# 15_PowerSupply.net
KiCad netlist of a schematic drawn in Altium Designer
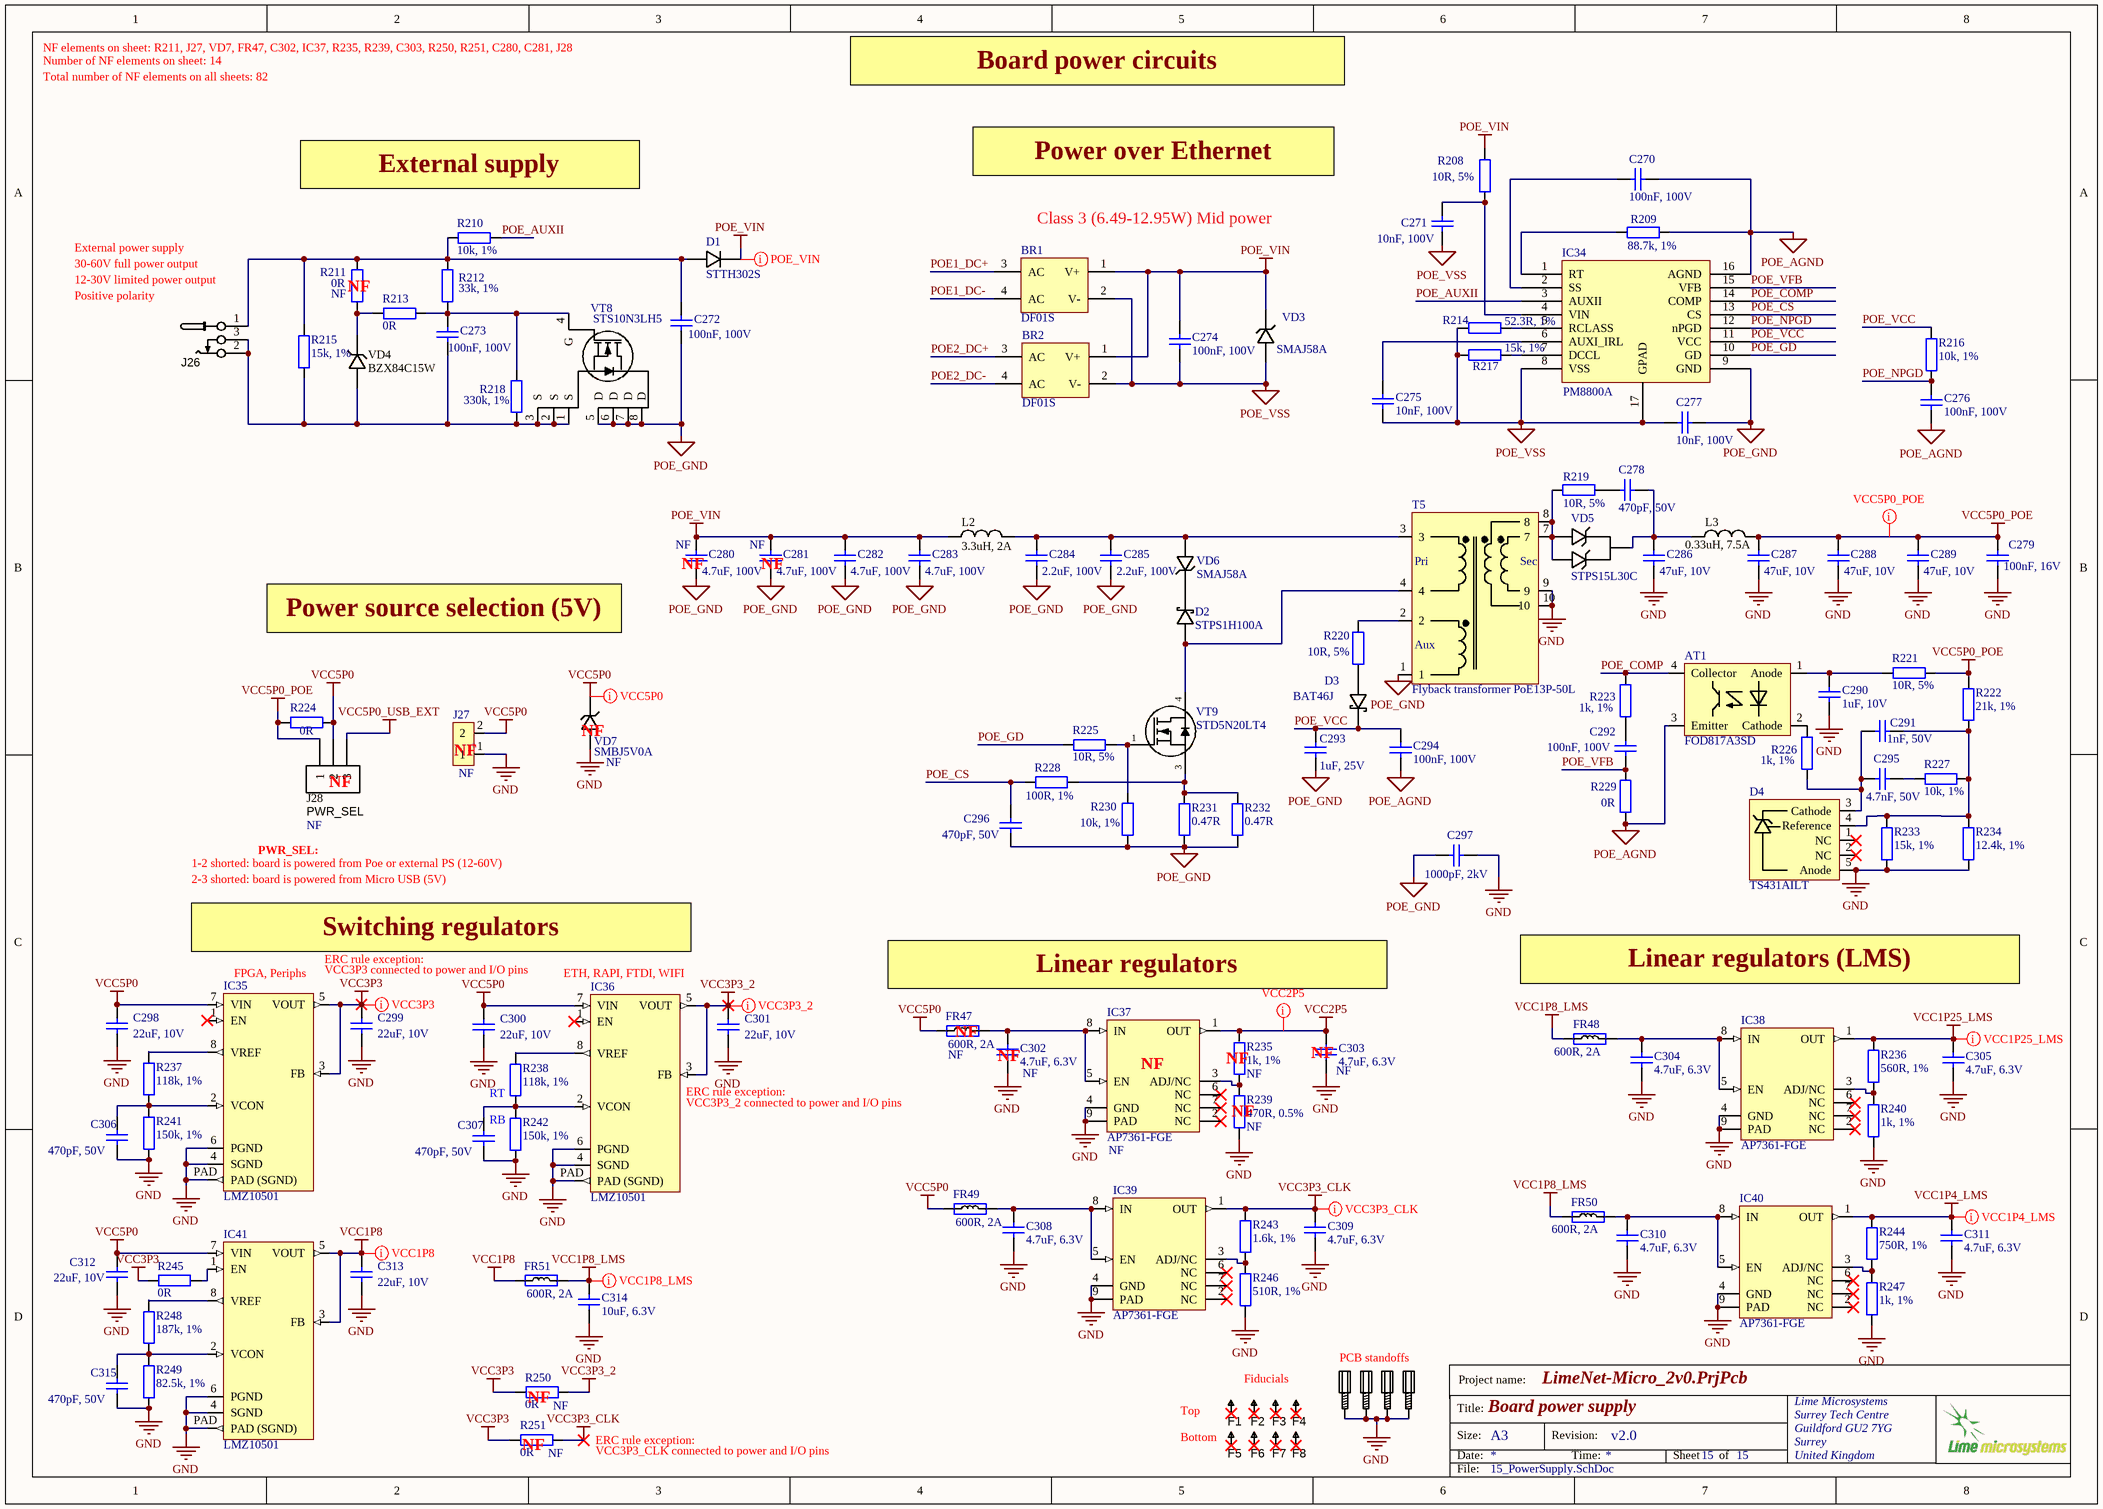
[diagram p0: 15_PowerSupply.SchDoc]

(export (version "E")
  (design (tool "Eeschema 10.0.6"))
  (components
    (comp (ref "AT1")
      (value "FOD817A3SD")
      (footprint "FOD817A3SD_optoisolator_FOD817")
      (fields (field (name "MANUFACTURER") "ON Semiconductor / Fairchild"))
      (libsource (lib "LimeMicroAltiumLib_schLib_r01") (part "FOD817A3SD_optoisolator"))
    )
    (comp (ref "BR1")
      (value "DF01S")
      (footprint "DF01S-T_RECTIFIER_BRIDGE_v1")
      (description "Diode Bridge")
      (fields (field (name "MANUFACTURER") "Diodes Incorporated"))
      (libsource (lib "Biblioteka_Ethernet") (part "Bridge2"))
    )
    (comp (ref "BR2")
      (value "DF01S")
      (footprint "DF01S-T_RECTIFIER_BRIDGE_v1")
      (description "Diode Bridge")
      (fields (field (name "MANUFACTURER") "Diodes Incorporated"))
      (libsource (lib "Biblioteka_Ethernet") (part "Bridge2"))
    )
    (comp (ref "C270")
      (value "100nF, 100V")
      (footprint "CAP0805")
      (fields
        (field (name "MANUFACTURER") "Murata Electronics North America")
        (field (name "TOLERANCE") "±10%")
      )
      (libsource (lib "LimeMicroAltium") (part "Cap_0805"))
    )
    (comp (ref "C271")
      (value "10nF, 100V")
      (footprint "CAP0603")
      (fields
        (field (name "TOLERANCE") "±10%")
        (field (name "MANUFACTURER") "Murata Electronics North America")
      )
      (libsource (lib "LimeFPGAboard_schLib") (part "Cap_0603"))
    )
    (comp (ref "C272")
      (value "100nF, 100V")
      (footprint "CAP0805")
      (fields
        (field (name "MANUFACTURER") "Murata Electronics North America")
        (field (name "TOLERANCE") "±10%")
      )
      (libsource (lib "LimeMicroAltium") (part "Cap_0805"))
    )
    (comp (ref "C273")
      (value "100nF, 100V")
      (footprint "CAP0805")
      (fields
        (field (name "MANUFACTURER") "Murata Electronics North America")
        (field (name "TOLERANCE") "±10%")
      )
      (libsource (lib "LimeMicroAltium") (part "Cap_0805"))
    )
    (comp (ref "C274")
      (value "100nF, 100V")
      (footprint "CAP0805")
      (fields
        (field (name "MANUFACTURER") "Murata Electronics North America")
        (field (name "TOLERANCE") "±10%")
      )
      (libsource (lib "LimeMicroAltium") (part "Cap_0805"))
    )
    (comp (ref "C275")
      (value "10nF, 100V")
      (footprint "CAP0603")
      (fields
        (field (name "TOLERANCE") "±10%")
        (field (name "MANUFACTURER") "Murata Electronics North America")
      )
      (libsource (lib "LimeFPGAboard_schLib") (part "Cap_0603"))
    )
    (comp (ref "C276")
      (value "100nF, 100V")
      (footprint "CAP0805")
      (fields
        (field (name "MANUFACTURER") "Murata Electronics North America")
        (field (name "TOLERANCE") "±10%")
      )
      (libsource (lib "LimeMicroAltium") (part "Cap_0805"))
    )
    (comp (ref "C277")
      (value "10nF, 100V")
      (footprint "CAP0603")
      (fields
        (field (name "TOLERANCE") "±10%")
        (field (name "MANUFACTURER") "Murata Electronics North America")
      )
      (libsource (lib "LimeFPGAboard_schLib") (part "Cap_0603"))
    )
    (comp (ref "C278")
      (value "470pF, 50V")
      (footprint "CAP0402")
      (fields
        (field (name "MANUFACTURER PART NUMBER") "C1005C0G1H471J050BA")
        (field (name "TOLERANCE") "±5%")
        (field (name "MANUFACTURER") "TDK Corporation")
      )
      (libsource (lib "LimeMicroAltiumLib_schLib") (part "Cap_0402"))
    )
    (comp (ref "C279")
      (value "100nF, 16V")
      (footprint "CAP0402")
      (fields
        (field (name "MANUFACTURER") "Murata Electronics")
        (field (name "TOLERANCE") "10 %")
        (field (name "MANUFACTURER PART NUMBER") "GRM155R71C104KA88D")
      )
      (libsource (lib "LimeMicroAltiumLib_schLib") (part "Cap_0402"))
    )
    (comp (ref "C280")
      (value "4.7uF, 100V")
      (footprint "CAP1210")
      (fields
        (field (name "ASSEMBLY INFO") "NF")
        (field (name "MANUFACTURER") "TDK Corporation")
        (field (name "TOLERANCE") "±20%")
      )
      (libsource (lib "LimeFPGAboard_schLib") (part "Cap_1206"))
    )
    (comp (ref "C281")
      (value "4.7uF, 100V")
      (footprint "CAP1210")
      (fields
        (field (name "ASSEMBLY INFO") "NF")
        (field (name "MANUFACTURER") "TDK Corporation")
        (field (name "TOLERANCE") "±20%")
      )
      (libsource (lib "LimeFPGAboard_schLib") (part "Cap_1206"))
    )
    (comp (ref "C282")
      (value "4.7uF, 100V")
      (footprint "CAP1210")
      (fields (field (name "MANUFACTURER") "TDK Corporation") (field (name "TOLERANCE") "±20%"))
      (libsource (lib "LimeFPGAboard_schLib") (part "Cap_1206"))
    )
    (comp (ref "C283")
      (value "4.7uF, 100V")
      (footprint "CAP1210")
      (fields (field (name "MANUFACTURER") "TDK Corporation") (field (name "TOLERANCE") "±20%"))
      (libsource (lib "LimeFPGAboard_schLib") (part "Cap_1206"))
    )
    (comp (ref "C284")
      (value "2.2uF, 100V")
      (footprint "CAP1206")
      (fields (field (name "MANUFACTURER") "TDK Corporation") (field (name "TOLERANCE") "±10%"))
      (libsource (lib "LimeFPGAboard_schLib") (part "Cap_1206"))
    )
    (comp (ref "C285")
      (value "2.2uF, 100V")
      (footprint "CAP1206")
      (fields (field (name "MANUFACTURER") "TDK Corporation") (field (name "TOLERANCE") "±10%"))
      (libsource (lib "LimeFPGAboard_schLib") (part "Cap_1206"))
    )
    (comp (ref "C286")
      (value "47uF, 10V")
      (footprint "CAP1206")
      (fields (field (name "TOLERANCE") "±20%") (field (name "MANUFACTURER") "TDK Corporation"))
      (libsource (lib "LimeFPGAboard_schLib") (part "Cap_1206"))
    )
    (comp (ref "C287")
      (value "47uF, 10V")
      (footprint "CAP1206")
      (fields (field (name "TOLERANCE") "±20%") (field (name "MANUFACTURER") "TDK Corporation"))
      (libsource (lib "LimeFPGAboard_schLib") (part "Cap_1206"))
    )
    (comp (ref "C288")
      (value "47uF, 10V")
      (footprint "CAP1206")
      (fields (field (name "TOLERANCE") "±20%") (field (name "MANUFACTURER") "TDK Corporation"))
      (libsource (lib "LimeFPGAboard_schLib") (part "Cap_1206"))
    )
    (comp (ref "C289")
      (value "47uF, 10V")
      (footprint "CAP1206")
      (fields (field (name "TOLERANCE") "±20%") (field (name "MANUFACTURER") "TDK Corporation"))
      (libsource (lib "LimeFPGAboard_schLib") (part "Cap_1206"))
    )
    (comp (ref "C290")
      (value "1uF, 10V")
      (footprint "CAP0402")
      (description "CAP CER 1UF 10V X5R 0402")
      (fields
        (field (name "MANUFACTURER") "Yageo")
        (field (name "MANUFACTURER PART NUMBER") "CC0402MRX5R6BB105")
      )
      (libsource (lib "LimeMicroAltiumLib_schLib") (part "Cap_0402"))
    )
    (comp (ref "C291")
      (value "1nF, 50V")
      (footprint "CAP0402")
      (fields
        (field (name "TOLERANCE") "±10%")
        (field (name "MANUFACTURER") "Murata Electronics North America")
      )
      (libsource (lib "LimeMicroAltiumLib_schLib") (part "Cap_0402"))
    )
    (comp (ref "C292")
      (value "100nF, 100V")
      (footprint "CAP0805")
      (fields
        (field (name "MANUFACTURER") "Murata Electronics North America")
        (field (name "TOLERANCE") "±10%")
      )
      (libsource (lib "LimeMicroAltium") (part "Cap_0805"))
    )
    (comp (ref "C293")
      (value "1uF, 25V")
      (footprint "CAP0603")
      (fields (field (name "MANUFACTURER") "Samsung Electro-Mechanics") (field (name "TOLERANCE") "±10%"))
      (libsource (lib "LimeMicroAltiumLib_schLib") (part "Cap_0603"))
    )
    (comp (ref "C294")
      (value "100nF, 100V")
      (footprint "CAP0805")
      (fields
        (field (name "MANUFACTURER") "Murata Electronics North America")
        (field (name "TOLERANCE") "±10%")
      )
      (libsource (lib "LimeMicroAltium") (part "Cap_0805"))
    )
    (comp (ref "C295")
      (value "4.7nF, 50V")
      (footprint "CAP0402")
      (fields
        (field (name "TOLERANCE") "±10%")
        (field (name "MANUFACTURER") "Murata Electronics North America")
      )
      (libsource (lib "LimeMicroAltiumLib_schLib") (part "Cap_0402"))
    )
    (comp (ref "C296")
      (value "470pF, 50V")
      (footprint "CAP0402")
      (fields
        (field (name "MANUFACTURER PART NUMBER") "C1005C0G1H471J050BA")
        (field (name "TOLERANCE") "±5%")
        (field (name "MANUFACTURER") "TDK Corporation")
      )
      (libsource (lib "LimeMicroAltiumLib_schLib") (part "Cap_0402"))
    )
    (comp (ref "C297")
      (value "1000pF, 2kV")
      (footprint "CAP1812")
      (fields (field (name "MANUFACTURER") "KEMET") (field (name "TOLERANCE") "±10%"))
      (libsource (lib "LimeFPGAboard_schLib") (part "Cap_1206"))
    )
    (comp (ref "C298")
      (value "22uF, 10V")
      (footprint "CAP0603")
      (fields (field (name "TOLERANCE") "20 %") (field (name "MANUFACTURER") "TDK Corporation"))
      (libsource (lib "LimeFPGAboard_schLib") (part "Cap_0603"))
    )
    (comp (ref "C299")
      (value "22uF, 10V")
      (footprint "CAP0603")
      (fields (field (name "TOLERANCE") "20 %") (field (name "MANUFACTURER") "TDK Corporation"))
      (libsource (lib "LimeFPGAboard_schLib") (part "Cap_0603"))
    )
    (comp (ref "C300")
      (value "22uF, 10V")
      (footprint "CAP0603")
      (fields (field (name "TOLERANCE") "20 %") (field (name "MANUFACTURER") "TDK Corporation"))
      (libsource (lib "LimeFPGAboard_schLib") (part "Cap_0603"))
    )
    (comp (ref "C301")
      (value "22uF, 10V")
      (footprint "CAP0603")
      (fields (field (name "TOLERANCE") "20 %") (field (name "MANUFACTURER") "TDK Corporation"))
      (libsource (lib "LimeFPGAboard_schLib") (part "Cap_0603"))
    )
    (comp (ref "C302")
      (value "4.7uF, 6.3V")
      (footprint "CAP0402")
      (fields
        (field (name "ASSEMBLY INFO") "NF")
        (field (name "MANUFACTURER") "Murata Electronics North America")
        (field (name "TOLERANCE") "±20%")
        (field (name "MANUFACTURER PART NUMBER") "GRM155R60J475ME87D")
      )
      (libsource (lib "LimeMicroAltiumLib_schLib") (part "Cap_0402"))
    )
    (comp (ref "C303")
      (value "4.7uF, 6.3V")
      (footprint "CAP0402")
      (fields
        (field (name "ASSEMBLY INFO") "NF")
        (field (name "MANUFACTURER") "Murata Electronics North America")
        (field (name "TOLERANCE") "±20%")
        (field (name "MANUFACTURER PART NUMBER") "GRM155R60J475ME87D")
      )
      (libsource (lib "LimeMicroAltiumLib_schLib") (part "Cap_0402"))
    )
    (comp (ref "C304")
      (value "4.7uF, 6.3V")
      (footprint "CAP0402")
      (fields
        (field (name "MANUFACTURER") "Murata Electronics North America")
        (field (name "TOLERANCE") "±20%")
        (field (name "MANUFACTURER PART NUMBER") "GRM155R60J475ME87D")
      )
      (libsource (lib "LimeMicroAltiumLib_schLib") (part "Cap_0402"))
    )
    (comp (ref "C305")
      (value "4.7uF, 6.3V")
      (footprint "CAP0402")
      (fields
        (field (name "MANUFACTURER") "Murata Electronics North America")
        (field (name "TOLERANCE") "±20%")
        (field (name "MANUFACTURER PART NUMBER") "GRM155R60J475ME87D")
      )
      (libsource (lib "LimeMicroAltiumLib_schLib") (part "Cap_0402"))
    )
    (comp (ref "C306")
      (value "470pF, 50V")
      (footprint "CAP0402")
      (fields
        (field (name "MANUFACTURER PART NUMBER") "C1005C0G1H471J050BA")
        (field (name "TOLERANCE") "±5%")
        (field (name "MANUFACTURER") "TDK Corporation")
      )
      (libsource (lib "LimeMicroAltiumLib_schLib") (part "Cap_0402"))
    )
    (comp (ref "C307")
      (value "470pF, 50V")
      (footprint "CAP0402")
      (fields
        (field (name "MANUFACTURER PART NUMBER") "C1005C0G1H471J050BA")
        (field (name "TOLERANCE") "±5%")
        (field (name "MANUFACTURER") "TDK Corporation")
      )
      (libsource (lib "LimeMicroAltiumLib_schLib") (part "Cap_0402"))
    )
    (comp (ref "C308")
      (value "4.7uF, 6.3V")
      (footprint "CAP0402")
      (fields
        (field (name "MANUFACTURER") "Murata Electronics North America")
        (field (name "TOLERANCE") "±20%")
        (field (name "MANUFACTURER PART NUMBER") "GRM155R60J475ME87D")
      )
      (libsource (lib "LimeMicroAltiumLib_schLib") (part "Cap_0402"))
    )
    (comp (ref "C309")
      (value "4.7uF, 6.3V")
      (footprint "CAP0402")
      (fields
        (field (name "MANUFACTURER") "Murata Electronics North America")
        (field (name "TOLERANCE") "±20%")
        (field (name "MANUFACTURER PART NUMBER") "GRM155R60J475ME87D")
      )
      (libsource (lib "LimeMicroAltiumLib_schLib") (part "Cap_0402"))
    )
    (comp (ref "C310")
      (value "4.7uF, 6.3V")
      (footprint "CAP0402")
      (fields
        (field (name "MANUFACTURER") "Murata Electronics North America")
        (field (name "TOLERANCE") "±20%")
        (field (name "MANUFACTURER PART NUMBER") "GRM155R60J475ME87D")
      )
      (libsource (lib "LimeMicroAltiumLib_schLib") (part "Cap_0402"))
    )
    (comp (ref "C311")
      (value "4.7uF, 6.3V")
      (footprint "CAP0402")
      (fields
        (field (name "MANUFACTURER") "Murata Electronics North America")
        (field (name "TOLERANCE") "±20%")
        (field (name "MANUFACTURER PART NUMBER") "GRM155R60J475ME87D")
      )
      (libsource (lib "LimeMicroAltiumLib_schLib") (part "Cap_0402"))
    )
    (comp (ref "C312")
      (value "22uF, 10V")
      (footprint "CAP0603")
      (fields (field (name "TOLERANCE") "20 %") (field (name "MANUFACTURER") "TDK Corporation"))
      (libsource (lib "LimeFPGAboard_schLib") (part "Cap_0603"))
    )
    (comp (ref "C313")
      (value "22uF, 10V")
      (footprint "CAP0603")
      (fields (field (name "TOLERANCE") "20 %") (field (name "MANUFACTURER") "TDK Corporation"))
      (libsource (lib "LimeFPGAboard_schLib") (part "Cap_0603"))
    )
    (comp (ref "C314")
      (value "10uF, 6.3V")
      (footprint "CAP0603")
      (fields (field (name "TOLERANCE") "±20%") (field (name "MANUFACTURER") "Yageo"))
      (libsource (lib "LimeFPGAboard_schLib") (part "Cap_0603"))
    )
    (comp (ref "C315")
      (value "470pF, 50V")
      (footprint "CAP0402")
      (fields
        (field (name "MANUFACTURER PART NUMBER") "C1005C0G1H471J050BA")
        (field (name "TOLERANCE") "±5%")
        (field (name "MANUFACTURER") "TDK Corporation")
      )
      (libsource (lib "LimeMicroAltiumLib_schLib") (part "Cap_0402"))
    )
    (comp (ref "D1")
      (value "STTH302S")
      (footprint "STTH302S_diode")
      (fields (field (name "MANUFACTURER") "STMicroelectronics"))
      (libsource (lib "LimeMicroAltiumLib_schLib_r01") (part "STTH302S_diode"))
    )
    (comp (ref "D2")
      (value "STPS1H100A")
      (footprint "STPS1H100A_shottky_diode")
      (fields (field (name "MANUFACTURER") "STMicroelectronics"))
      (libsource (lib "LimeMicroAltiumLib_schLib_r01") (part "STPS1H100A_shottky_diode"))
    )
    (comp (ref "D3")
      (value "BAT46J")
      (footprint "BAT46JFILM_shottky_diode_SOD323")
      (fields (field (name "MANUFACTURER") "STMicroelectronics") (field (name "BASE PART NUMBER") "BAT46"))
      (libsource (lib "LimeMicroAltiumLib_schLib_r01") (part "BAT46JFILM_shottky_diode"))
    )
    (comp (ref "D4")
      (value "TS431AILT")
      (footprint "SOT23-5")
      (fields (field (name "MANUFACTURER") "STMicroelectronics") (field (name "TOLERANCE") "1%"))
      (libsource (lib "LimeMicroAltiumLib_schLib_r01") (part "TS431AILT_VREF_ADJ"))
    )
    (comp (ref "F1")
      (value "Fiducial")
      (footprint "Fiducial")
      (libsource (lib "VGTU_Altium_lib") (part "Fiducial"))
    )
    (comp (ref "F2")
      (value "Fiducial")
      (footprint "Fiducial")
      (libsource (lib "VGTU_Altium_lib") (part "Fiducial"))
    )
    (comp (ref "F3")
      (value "Fiducial")
      (footprint "Fiducial")
      (libsource (lib "VGTU_Altium_lib") (part "Fiducial"))
    )
    (comp (ref "F4")
      (value "Fiducial")
      (footprint "Fiducial")
      (libsource (lib "VGTU_Altium_lib") (part "Fiducial"))
    )
    (comp (ref "F5")
      (value "Fiducial")
      (footprint "Fiducial")
      (libsource (lib "VGTU_Altium_lib") (part "Fiducial"))
    )
    (comp (ref "F6")
      (value "Fiducial")
      (footprint "Fiducial")
      (libsource (lib "VGTU_Altium_lib") (part "Fiducial"))
    )
    (comp (ref "F7")
      (value "Fiducial")
      (footprint "Fiducial")
      (libsource (lib "VGTU_Altium_lib") (part "Fiducial"))
    )
    (comp (ref "F8")
      (value "Fiducial")
      (footprint "Fiducial")
      (libsource (lib "VGTU_Altium_lib") (part "Fiducial"))
    )
    (comp (ref "FR47")
      (value "600R, 2A")
      (footprint "RES0805")
      (fields (field (name "MANUFACTURER") "TDK Corporation") (field (name "ASSEMBLY INFO") "NF"))
      (libsource (lib "LimeMicroAltiumLib_schLib") (part "Ferrite"))
    )
    (comp (ref "FR48")
      (value "600R, 2A")
      (footprint "RES0805")
      (fields (field (name "MANUFACTURER") "TDK Corporation"))
      (libsource (lib "LimeMicroAltiumLib_schLib") (part "Ferrite"))
    )
    (comp (ref "FR49")
      (value "600R, 2A")
      (footprint "RES0805")
      (fields (field (name "MANUFACTURER") "TDK Corporation"))
      (libsource (lib "LimeMicroAltiumLib_schLib") (part "Ferrite"))
    )
    (comp (ref "FR50")
      (value "600R, 2A")
      (footprint "RES0805")
      (fields (field (name "MANUFACTURER") "TDK Corporation"))
      (libsource (lib "LimeMicroAltiumLib_schLib") (part "Ferrite"))
    )
    (comp (ref "FR51")
      (value "600R, 2A")
      (footprint "RES0805")
      (fields (field (name "MANUFACTURER") "TDK Corporation"))
      (libsource (lib "LimeMicroAltiumLib_schLib") (part "Ferrite"))
    )
    (comp (ref "IC34")
      (value "PM8800A")
      (footprint "PM8800A_HTSSOP16")
      (fields (field (name "MANUFACTURER") "STMicroelectronics"))
      (libsource (lib "Biblioteka_Ethernet") (part "PM8800A"))
    )
    (comp (ref "IC35")
      (value "LMZ10501")
      (footprint "LMZ10501")
      (fields
        (field (name "MANUFACTURER") "Texas Instruments")
        (field (name "MANUFACTURER PART NUMBER") "LMZ10501SILR")
      )
      (libsource (lib "LimeMicroAltiumLib_schLib") (part "LMZ10501"))
    )
    (comp (ref "IC36")
      (value "LMZ10501")
      (footprint "LMZ10501")
      (fields
        (field (name "MANUFACTURER") "Texas Instruments")
        (field (name "MANUFACTURER PART NUMBER") "LMZ10501SILR")
      )
      (libsource (lib "LimeMicroAltiumLib_schLib") (part "LMZ10501"))
    )
    (comp (ref "IC37")
      (value "AP7361-FGE")
      (footprint "AP7361")
      (fields
        (field (name "MANUFACTURER PART NUMBER") "AP7361-FGE-7")
        (field (name "MANUFACTURER") "Diodes Incorporated")
        (field (name "ASSEMBLY INFO") "NF")
      )
      (libsource (lib "LimeMicroAltiumLib_schLib") (part "AP7361"))
    )
    (comp (ref "IC38")
      (value "AP7361-FGE")
      (footprint "AP7361")
      (fields (field (name "MANUFACTURER") "Diodes Incorporated"))
      (libsource (lib "") (part "AP7361_1"))
    )
    (comp (ref "IC39")
      (value "AP7361-FGE")
      (footprint "AP7361")
      (fields (field (name "MANUFACTURER") "Diodes Incorporated"))
      (libsource (lib "") (part "AP7361_1"))
    )
    (comp (ref "IC40")
      (value "AP7361-FGE")
      (footprint "AP7361")
      (fields (field (name "MANUFACTURER") "Diodes Incorporated"))
      (libsource (lib "") (part "AP7361_1"))
    )
    (comp (ref "IC41")
      (value "LMZ10501")
      (footprint "LMZ10501")
      (fields
        (field (name "MANUFACTURER") "Texas Instruments")
        (field (name "MANUFACTURER PART NUMBER") "LMZ10501SILR")
      )
      (libsource (lib "LimeMicroAltiumLib_schLib") (part "LMZ10501"))
    )
    (comp (ref "J26")
      (value "CONN_PWR_JACK_2.1x5.5mm")
      (footprint "CONN_PWR_JACK_v2")
      (description "CONN POWERJACK MINI R/A PCMT")
      (fields (field (name "MANUFACTURER") "Switchcraft"))
      (libsource (lib "LimeFPGAboard_schLib") (part "CONN_PWR_JACK_2.1x5.5mm"))
    )
    (comp (ref "J27")
      (value "~")
      (footprint "HDR_1x2_NO_SILK")
      (fields (field (name "ASSEMBLY INFO") "NF") (field (name "MANUFACTURER") "3M"))
      (libsource (lib "LimeFPGAboard_schLib") (part "Jumper"))
    )
    (comp (ref "J28")
      (value "PWR_SEL")
      (footprint "HDR_1x3_NO_SILK")
      (description "Header, 3-pin")
      (fields (field (name "MANUFACTURER") "FCI") (field (name "ASSEMBLY INFO") "NF"))
      (libsource (lib "LimeMicroAltiumLib_schLib") (part "Header3P"))
    )
    (comp (ref "L2")
      (value "3.3uH, 2A")
      (footprint "NRS4018T3R3MDGJ_inductor")
      (fields (field (name "MANUFACTURER") "Taiyo Yuden") (field (name "TOLERANCE") "±20%"))
      (libsource (lib "LimeMicroAltiumLib_schLib") (part "Inductor_0603"))
    )
    (comp (ref "L3")
      (value "0.33uH, 7.5A")
      (footprint "PA4336.331NLT_inductor")
      (fields
        (field (name "TOLERANCE") "±30%")
        (field (name "MANUFACTURER") "Pulse Electronics Power")
        (field (name "MANUFACTURER PART NUMBER") "PA4336.331NLT")
      )
      (libsource (lib "LimeMicroAltiumLib_schLib") (part "Inductor_0603"))
    )
    (comp (ref "MECH5")
      (value "# pcs.")
      (footprint "PCB_standoff")
      (description "STANDOFF M/F MET 5MM HEX 10MM L")
      (fields (field (name "MANUFACTURER") "FIX&FASTEN"))
      (libsource (lib "LimeMicroAltiumLib_schLib") (part "STANDOFF_M-F_THREADED_M3x8x10mm_HEX_5mm dia"))
    )
    (comp (ref "MECH6")
      (value "# pcs.")
      (footprint "PCB_standoff")
      (description "STANDOFF M/F MET 5MM HEX 10MM L")
      (fields (field (name "MANUFACTURER") "FIX&FASTEN"))
      (libsource (lib "LimeMicroAltiumLib_schLib") (part "STANDOFF_M-F_THREADED_M3x8x10mm_HEX_5mm dia"))
    )
    (comp (ref "MECH7")
      (value "# pcs.")
      (footprint "PCB_standoff")
      (description "STANDOFF M/F MET 5MM HEX 10MM L")
      (fields (field (name "MANUFACTURER") "FIX&FASTEN"))
      (libsource (lib "LimeMicroAltiumLib_schLib") (part "STANDOFF_M-F_THREADED_M3x8x10mm_HEX_5mm dia"))
    )
    (comp (ref "MECH8")
      (value "# pcs.")
      (footprint "PCB_standoff")
      (description "STANDOFF M/F MET 5MM HEX 10MM L")
      (fields (field (name "MANUFACTURER") "FIX&FASTEN"))
      (libsource (lib "LimeMicroAltiumLib_schLib") (part "STANDOFF_M-F_THREADED_M3x8x10mm_HEX_5mm dia"))
    )
    (comp (ref "R208")
      (value "10R, 5%")
      (footprint "RES0402")
      (fields (field (name "TOLERANCE") "±5%") (field (name "MANUFACTURER") "Yageo"))
      (libsource (lib "LimeMicroAltiumLib_schLib") (part "Res_0402"))
    )
    (comp (ref "R209")
      (value "88.7k, 1%")
      (footprint "RES0402")
      (fields (field (name "TOLERANCE") "±1%") (field (name "MANUFACTURER") "Yageo"))
      (libsource (lib "LimeMicroAltiumLib_schLib") (part "Res_0402"))
    )
    (comp (ref "R210")
      (value "10k, 1%")
      (footprint "RES0402")
      (fields (field (name "MANUFACTURER") "Yageo") (field (name "TOLERANCE") "±1%"))
      (libsource (lib "LimeMicroAltiumLib_schLib") (part "Res_0402"))
    )
    (comp (ref "R211")
      (value "0R")
      (footprint "RES0402")
      (fields (field (name "MANUFACTURER") "Yageo") (field (name "ASSEMBLY INFO") "NF"))
      (libsource (lib "LimeFPGAboard_schLib") (part "Res_0402"))
    )
    (comp (ref "R212")
      (value "33k, 1%")
      (footprint "RES0402")
      (fields (field (name "TOLERANCE") "±1%") (field (name "MANUFACTURER") "Yageo"))
      (libsource (lib "LimeMicroAltiumLib_schLib") (part "Res_0402"))
    )
    (comp (ref "R213")
      (value "0R")
      (footprint "RES0402")
      (fields (field (name "MANUFACTURER") "Yageo"))
      (libsource (lib "LimeFPGAboard_schLib") (part "Res_0402"))
    )
    (comp (ref "R214")
      (value "52.3R, 1%")
      (footprint "RES0805")
      (fields
        (field (name "MANUFACTURER PART NUMBER") "RMCF0805FT52R3")
        (field (name "MANUFACTURER") "Stackpole Electronics Inc.")
        (field (name "TOLERANCE") "±1%")
      )
      (libsource (lib "LimeMicroAltiumLib_schLib") (part "Res_0402"))
    )
    (comp (ref "R215")
      (value "15k, 1%")
      (footprint "RES0402")
      (fields (field (name "TOLERANCE") "±1%") (field (name "MANUFACTURER") "Yageo"))
      (libsource (lib "LimeMicroAltiumLib_schLib") (part "Res_0402"))
    )
    (comp (ref "R216")
      (value "10k, 1%")
      (footprint "RES0402")
      (fields (field (name "MANUFACTURER") "Yageo") (field (name "TOLERANCE") "±1%"))
      (libsource (lib "LimeMicroAltiumLib_schLib") (part "Res_0402"))
    )
    (comp (ref "R217")
      (value "15k, 1%")
      (footprint "RES0402")
      (fields (field (name "TOLERANCE") "±1%") (field (name "MANUFACTURER") "Yageo"))
      (libsource (lib "LimeMicroAltiumLib_schLib") (part "Res_0402"))
    )
    (comp (ref "R218")
      (value "330k, 1%")
      (footprint "RES0402")
      (fields (field (name "TOLERANCE") "±1%") (field (name "MANUFACTURER") "Yageo"))
      (libsource (lib "LimeMicroAltiumLib_schLib") (part "Res_0402"))
    )
    (comp (ref "R219")
      (value "10R, 5%")
      (footprint "RES0402")
      (fields (field (name "TOLERANCE") "±5%") (field (name "MANUFACTURER") "Yageo"))
      (libsource (lib "LimeMicroAltiumLib_schLib") (part "Res_0402"))
    )
    (comp (ref "R220")
      (value "10R, 5%")
      (footprint "RES0402")
      (fields (field (name "TOLERANCE") "±5%") (field (name "MANUFACTURER") "Yageo"))
      (libsource (lib "LimeMicroAltiumLib_schLib") (part "Res_0402"))
    )
    (comp (ref "R221")
      (value "10R, 5%")
      (footprint "RES0402")
      (fields (field (name "TOLERANCE") "±5%") (field (name "MANUFACTURER") "Yageo"))
      (libsource (lib "LimeMicroAltiumLib_schLib") (part "Res_0402"))
    )
    (comp (ref "R222")
      (value "21k, 1%")
      (footprint "RES0402")
      (fields (field (name "TOLERANCE") "±1%") (field (name "MANUFACTURER") "Samsung Electro-Mechanics"))
      (libsource (lib "LimeMicroAltiumLib_schLib") (part "Res_0402"))
    )
    (comp (ref "R223")
      (value "1k, 1%")
      (footprint "RES0402")
      (fields (field (name "MANUFACTURER") "Stackpole Electronics Inc") (field (name "TOLERANCE") "±1%"))
      (libsource (lib "LimeMicroAltiumLib_schLib") (part "Res_0402"))
    )
    (comp (ref "R224")
      (value "0R")
      (footprint "RES0805")
      (fields (field (name "MANUFACTURER") "Vishay Dale") (field (name "TOLERANCE") "Jumper"))
      (libsource (lib "LimeMicroAltiumLib_schLib") (part "Res_0402"))
    )
    (comp (ref "R225")
      (value "10R, 5%")
      (footprint "RES0402")
      (fields (field (name "TOLERANCE") "±5%") (field (name "MANUFACTURER") "Yageo"))
      (libsource (lib "LimeMicroAltiumLib_schLib") (part "Res_0402"))
    )
    (comp (ref "R226")
      (value "1k, 1%")
      (footprint "RES0402")
      (fields (field (name "MANUFACTURER") "Stackpole Electronics Inc") (field (name "TOLERANCE") "±1%"))
      (libsource (lib "LimeMicroAltiumLib_schLib") (part "Res_0402"))
    )
    (comp (ref "R227")
      (value "10k, 1%")
      (footprint "RES0402")
      (fields (field (name "MANUFACTURER") "Yageo") (field (name "TOLERANCE") "±1%"))
      (libsource (lib "LimeMicroAltiumLib_schLib") (part "Res_0402"))
    )
    (comp (ref "R228")
      (value "100R, 1%")
      (footprint "RES0402")
      (fields (field (name "TOLERANCE") "±1%") (field (name "MANUFACTURER") "Stackpole Electronics Inc."))
      (libsource (lib "LimeMicroAltiumLib_schLib") (part "Res_0402"))
    )
    (comp (ref "R229")
      (value "0R")
      (footprint "RES0402")
      (fields (field (name "MANUFACTURER") "Yageo") (field (name "TOLERANCE") "Jumper"))
      (libsource (lib "LimeMicroAltiumLib_schLib") (part "Res_0402"))
    )
    (comp (ref "R230")
      (value "10k, 1%")
      (footprint "RES0402")
      (fields (field (name "MANUFACTURER") "Yageo") (field (name "TOLERANCE") "±1%"))
      (libsource (lib "LimeMicroAltiumLib_schLib") (part "Res_0402"))
    )
    (comp (ref "R231")
      (value "0.47R")
      (footprint "RES0805")
      (fields (field (name "TOLERANCE") "±5%") (field (name "MANUFACTURER") "Yageo"))
      (libsource (lib "LimeMicroAltiumLib_schLib") (part "Res_0402"))
    )
    (comp (ref "R232")
      (value "0.47R")
      (footprint "RES0805")
      (fields (field (name "TOLERANCE") "±5%") (field (name "MANUFACTURER") "Yageo"))
      (libsource (lib "LimeMicroAltiumLib_schLib") (part "Res_0402"))
    )
    (comp (ref "R233")
      (value "15k, 1%")
      (footprint "RES0402")
      (fields (field (name "TOLERANCE") "±1%") (field (name "MANUFACTURER") "Yageo"))
      (libsource (lib "LimeMicroAltiumLib_schLib") (part "Res_0402"))
    )
    (comp (ref "R234")
      (value "12.4k, 1%")
      (footprint "RES0402")
      (fields
        (field (name "MANUFACTURER") "Yageo")
        (field (name "MANUFACTURER PART NUMBER") "RC0402FR-0712K4L")
        (field (name "TOLERANCE") "±0.1%")
      )
      (libsource (lib "LimeMicroAltiumLib_schLib") (part "Res_0402"))
    )
    (comp (ref "R235")
      (value "1k, 1%")
      (footprint "RES0402")
      (fields
        (field (name "ASSEMBLY INFO") "NF")
        (field (name "MANUFACTURER") "Stackpole Electronics Inc")
        (field (name "TOLERANCE") "±1%")
      )
      (libsource (lib "LimeMicroAltiumLib_schLib") (part "Res_0402"))
    )
    (comp (ref "R236")
      (value "560R, 1%")
      (footprint "RES0402")
      (fields
        (field (name "MANUFACTURER PART NUMBER") "CRCW0402560RFKED")
        (field (name "TOLERANCE") "±1%")
        (field (name "MANUFACTURER") "Vishay Dale")
      )
      (libsource (lib "LimeMicroAltiumLib_schLib") (part "Res_0402"))
    )
    (comp (ref "R237")
      (value "118k, 1%")
      (footprint "RES0402")
      (fields
        (field (name "MANUFACTURER") "Yageo")
        (field (name "MANUFACTURER PART NUMBER") "RC0402FR-07118KL")
        (field (name "TOLERANCE") "±1%")
      )
      (libsource (lib "LimeMicroAltiumLib_schLib") (part "Res_0402"))
    )
    (comp (ref "R238")
      (value "118k, 1%")
      (footprint "RES0402")
      (fields
        (field (name "MANUFACTURER") "Yageo")
        (field (name "MANUFACTURER PART NUMBER") "RC0402FR-07118KL")
        (field (name "TOLERANCE") "±1%")
      )
      (libsource (lib "LimeMicroAltiumLib_schLib") (part "Res_0402"))
    )
    (comp (ref "R239")
      (value "470R, 0.5%")
      (footprint "RES0402")
      (fields
        (field (name "ASSEMBLY INFO") "NF")
        (field (name "TOLERANCE") "±0.5%")
        (field (name "MANUFACTURER") "Panasonic Electronic Components")
      )
      (libsource (lib "LimeMicroAltiumLib_schLib") (part "Res_0402"))
    )
    (comp (ref "R240")
      (value "1k, 1%")
      (footprint "RES0402")
      (fields (field (name "MANUFACTURER") "Stackpole Electronics Inc") (field (name "TOLERANCE") "±1%"))
      (libsource (lib "LimeMicroAltiumLib_schLib") (part "Res_0402"))
    )
    (comp (ref "R241")
      (value "150k, 1%")
      (footprint "RES0402")
      (fields (field (name "TOLERANCE") "±5%") (field (name "MANUFACTURER") "Yageo"))
      (libsource (lib "LimeMicroAltiumLib_schLib") (part "Res_0402"))
    )
    (comp (ref "R242")
      (value "150k, 1%")
      (footprint "RES0402")
      (fields (field (name "TOLERANCE") "±5%") (field (name "MANUFACTURER") "Yageo"))
      (libsource (lib "LimeMicroAltiumLib_schLib") (part "Res_0402"))
    )
    (comp (ref "R243")
      (value "1.6k, 1%")
      (footprint "RES0402")
      (fields
        (field (name "TOLERANCE") "±1%")
        (field (name "MANUFACTURER PART NUMBER") "RC0402FR-071K6L")
        (field (name "MANUFACTURER") "Yageo")
      )
      (libsource (lib "LimeMicroAltiumLib_schLib") (part "Res_0402"))
    )
    (comp (ref "R244")
      (value "750R, 1%")
      (footprint "RES0402")
      (fields
        (field (name "TOLERANCE") "±1%")
        (field (name "MANUFACTURER PART NUMBER") "RC0402FR-07750RL")
        (field (name "MANUFACTURER") "Yageo")
      )
      (libsource (lib "LimeMicroAltiumLib_schLib") (part "Res_0402"))
    )
    (comp (ref "R245")
      (value "0R")
      (footprint "RES0402")
      (fields (field (name "MANUFACTURER") "Yageo") (field (name "TOLERANCE") "Jumper"))
      (libsource (lib "LimeMicroAltiumLib_schLib") (part "Res_0402"))
    )
    (comp (ref "R246")
      (value "510R, 1%")
      (footprint "RES0402")
      (fields
        (field (name "TOLERANCE") "±1%")
        (field (name "MANUFACTURER PART NUMBER") "RC0402FR-07510RL")
        (field (name "MANUFACTURER") "Yageo")
      )
      (libsource (lib "LimeMicroAltiumLib_schLib") (part "Res_0402"))
    )
    (comp (ref "R247")
      (value "1k, 1%")
      (footprint "RES0402")
      (fields (field (name "MANUFACTURER") "Stackpole Electronics Inc") (field (name "TOLERANCE") "±1%"))
      (libsource (lib "LimeMicroAltiumLib_schLib") (part "Res_0402"))
    )
    (comp (ref "R248")
      (value "187k, 1%")
      (footprint "RES0402")
      (fields (field (name "TOLERANCE") "±1%") (field (name "MANUFACTURER") "Yageo"))
      (libsource (lib "LimeMicroAltiumLib_schLib") (part "Res_0402"))
    )
    (comp (ref "R249")
      (value "82.5k, 1%")
      (footprint "RES0402")
      (fields (field (name "TOLERANCE") "±1%") (field (name "MANUFACTURER") "Yageo"))
      (libsource (lib "LimeMicroAltiumLib_schLib") (part "Res_0402"))
    )
    (comp (ref "R250")
      (value "0R")
      (footprint "RES0805")
      (fields
        (field (name "ASSEMBLY INFO") "NF")
        (field (name "MANUFACTURER") "Vishay Dale")
        (field (name "TOLERANCE") "Jumper")
      )
      (libsource (lib "LimeMicroAltiumLib_schLib") (part "Res_0402"))
    )
    (comp (ref "R251")
      (value "0R")
      (footprint "RES0805")
      (fields
        (field (name "ASSEMBLY INFO") "NF")
        (field (name "MANUFACTURER") "Vishay Dale")
        (field (name "TOLERANCE") "Jumper")
      )
      (libsource (lib "LimeMicroAltiumLib_schLib") (part "Res_0402"))
    )
    (comp (ref "T5")
      (value "Flyback transformer PoE13P-50L")
      (footprint "PoE13P-50L_Flyback_transformer")
      (fields (field (name "MANUFACTURER") "Coilcraft"))
      (libsource (lib "LimeMicroAltiumLib_schLib_r01") (part "PoE13P-50L_Flyback_transformer_1"))
    )
    (comp (ref "VD3")
      (value "SMAJ58A")
      (footprint "SMAJ58A_shottky_diode")
      (description "SMAJ58A-TR")
      (fields (field (name "BASE PART NUMBER") "SMAJ58") (field (name "MANUFACTURER") "Diodes Incorporated"))
      (libsource (lib "LimeMicroAltium") (part "DIODE_TVS_UNIDIR"))
    )
    (comp (ref "VD4")
      (value "BZX84C15W")
      (footprint "SOT323")
      (fields (field (name "MANUFACTURER") "Diodes") (field (name "TOLERANCE") "6%"))
      (libsource (lib "LimeMicroAltiumLib_schLib_r01") (part "BZX84C15W_DIODE_ZENER"))
    )
    (comp (ref "VD5")
      (value "STPS15L30C")
      (footprint "STPS15L30C_shottky_rectifier_DPAK")
      (fields (field (name "MANUFACTURER") "STMicroelectronics"))
      (libsource (lib "LimeMicroAltiumLib_schLib_r01") (part "STPS15L30C_shottky_rectifier"))
    )
    (comp (ref "VD6")
      (value "SMAJ58A")
      (footprint "SMAJ58A_shottky_diode")
      (description "SMAJ58A-TR")
      (fields (field (name "BASE PART NUMBER") "SMAJ58") (field (name "MANUFACTURER") "Diodes Incorporated"))
      (libsource (lib "LimeMicroAltium") (part "DIODE_TVS_UNIDIR"))
    )
    (comp (ref "VD7")
      (value "SMBJ5V0A")
      (footprint "SMAJ12CA-13-F")
      (description "SMAJ12CA-13-F")
      (fields
        (field (name "MANUFACTURER") "ON Semiconductor")
        (field (name "BASE PART NUMBER") "SMBJ5V0")
        (field (name "ASSEMBLY INFO") "NF")
      )
      (libsource (lib "LimeMicroAltiumLib_schLib_r01") (part "DIODE_TVS_UNIDIR"))
    )
    (comp (ref "VT8")
      (value "STS10N3LH5")
      (footprint "STS10P3LLH6_PMOS_SO8")
      (fields (field (name "MANUFACTURER") "STMicroelectronics"))
      (libsource (lib "LimeMicroAltiumLib_schLib_r01") (part "STS10N3LH5_NMOS"))
    )
    (comp (ref "VT9")
      (value "STD5N20LT4")
      (footprint "STD5N20LT4_NMOS_DPAK")
      (fields (field (name "MANUFACTURER") "STMicroelectronics"))
      (libsource (lib "LimeMicroAltiumLib_schLib_r01") (part "STD5N20LT4_NMOS"))
    )
  )
  (nets
    (net (code "1") (name "/POE1_DC+") (class "Default")
      (node (ref "BR1") (pin "3") (pinfunction "AC_3") (pintype "passive"))
    )
    (net (code "2") (name "/POE1_DC-") (class "Default")
      (node (ref "BR1") (pin "4") (pinfunction "AC_4") (pintype "passive"))
    )
    (net (code "3") (name "/POE2_DC+") (class "Default")
      (node (ref "BR2") (pin "3") (pinfunction "AC_3") (pintype "passive"))
    )
    (net (code "4") (name "/POE2_DC-") (class "Default")
      (node (ref "BR2") (pin "4") (pinfunction "AC_4") (pintype "passive"))
    )
    (net (code "5") (name "/POE_AUXII") (class "Default")
      (node (ref "IC34") (pin "3") (pinfunction "AUXII_3") (pintype "passive"))
      (node (ref "R210") (pin "2") (pinfunction "2_2") (pintype "passive"))
    )
    (net (code "6") (name "/POE_COMP") (class "Default")
      (node (ref "AT1") (pin "4") (pinfunction "Collector_4") (pintype "passive"))
      (node (ref "IC34") (pin "14") (pinfunction "COMP_14") (pintype "passive"))
      (node (ref "R223") (pin "2") (pinfunction "2_2") (pintype "passive"))
    )
    (net (code "7") (name "/POE_CS") (class "Default")
      (node (ref "C296") (pin "1") (pinfunction "1_1") (pintype "passive"))
      (node (ref "IC34") (pin "13") (pinfunction "CS_13") (pintype "passive"))
      (node (ref "R228") (pin "1") (pinfunction "1_1") (pintype "passive"))
    )
    (net (code "8") (name "/POE_GD") (class "Default")
      (node (ref "IC34") (pin "10") (pinfunction "GD_10") (pintype "passive"))
      (node (ref "R225") (pin "1") (pinfunction "1_1") (pintype "passive"))
    )
    (net (code "9") (name "/POE_NPGD") (class "Default")
      (node (ref "C276") (pin "2") (pinfunction "2_2") (pintype "passive"))
      (node (ref "IC34") (pin "12") (pinfunction "nPGD_12") (pintype "passive"))
      (node (ref "R216") (pin "1") (pinfunction "1_1") (pintype "passive"))
    )
    (net (code "10") (name "/POE_VCC") (class "Default")
      (node (ref "C293") (pin "2") (pinfunction "2_2") (pintype "passive"))
      (node (ref "C294") (pin "2") (pinfunction "2_2") (pintype "passive"))
      (node (ref "D3") (pin "C") (pinfunction "C_C") (pintype "passive"))
      (node (ref "IC34") (pin "11") (pinfunction "VCC_11") (pintype "passive"))
      (node (ref "R216") (pin "2") (pinfunction "2_2") (pintype "passive"))
    )
    (net (code "11") (name "/POE_VFB") (class "Default")
      (node (ref "C292") (pin "1") (pinfunction "1_1") (pintype "passive"))
      (node (ref "IC34") (pin "15") (pinfunction "VFB_15") (pintype "passive"))
      (node (ref "R229") (pin "1") (pinfunction "1_1") (pintype "passive"))
    )
    (net (code "12") (name "GND") (class "Default")
      (node (ref "C279") (pin "1") (pinfunction "1_1") (pintype "passive"))
      (node (ref "C286") (pin "1") (pinfunction "1_1") (pintype "passive"))
      (node (ref "C287") (pin "1") (pinfunction "1_1") (pintype "passive"))
      (node (ref "C288") (pin "1") (pinfunction "1_1") (pintype "passive"))
      (node (ref "C289") (pin "1") (pinfunction "1_1") (pintype "passive"))
      (node (ref "C290") (pin "1") (pinfunction "1_1") (pintype "passive"))
      (node (ref "C297") (pin "1") (pinfunction "1_1") (pintype "passive"))
      (node (ref "C298") (pin "1") (pinfunction "1_1") (pintype "passive"))
      (node (ref "C299") (pin "1") (pinfunction "1_1") (pintype "passive"))
      (node (ref "C300") (pin "1") (pinfunction "1_1") (pintype "passive"))
      (node (ref "C301") (pin "1") (pinfunction "1_1") (pintype "passive"))
      (node (ref "C302") (pin "1") (pinfunction "1_1") (pintype "passive"))
      (node (ref "C303") (pin "1") (pinfunction "1_1") (pintype "passive"))
      (node (ref "C304") (pin "1") (pinfunction "1_1") (pintype "passive"))
      (node (ref "C305") (pin "1") (pinfunction "1_1") (pintype "passive"))
      (node (ref "C306") (pin "2") (pinfunction "2_2") (pintype "passive"))
      (node (ref "C307") (pin "2") (pinfunction "2_2") (pintype "passive"))
      (node (ref "C308") (pin "1") (pinfunction "1_1") (pintype "passive"))
      (node (ref "C309") (pin "1") (pinfunction "1_1") (pintype "passive"))
      (node (ref "C310") (pin "1") (pinfunction "1_1") (pintype "passive"))
      (node (ref "C311") (pin "1") (pinfunction "1_1") (pintype "passive"))
      (node (ref "C312") (pin "1") (pinfunction "1_1") (pintype "passive"))
      (node (ref "C313") (pin "1") (pinfunction "1_1") (pintype "passive"))
      (node (ref "C314") (pin "1") (pinfunction "1_1") (pintype "passive"))
      (node (ref "C315") (pin "2") (pinfunction "2_2") (pintype "passive"))
      (node (ref "D4") (pin "5") (pinfunction "Anode_5") (pintype "passive"))
      (node (ref "IC35") (pin "4") (pinfunction "SGND_4") (pintype "passive"))
      (node (ref "IC35") (pin "6") (pinfunction "PGND_6") (pintype "passive"))
      (node (ref "IC35") (pin "PAD") (pinfunction "PAD_(SGND)_PAD") (pintype "output"))
      (node (ref "IC36") (pin "4") (pinfunction "SGND_4") (pintype "passive"))
      (node (ref "IC36") (pin "6") (pinfunction "PGND_6") (pintype "passive"))
      (node (ref "IC36") (pin "PAD") (pinfunction "PAD_(SGND)_PAD") (pintype "output"))
      (node (ref "IC37") (pin "4") (pinfunction "GND_4") (pintype "passive"))
      (node (ref "IC37") (pin "9") (pinfunction "PAD_9") (pintype "passive"))
      (node (ref "IC38") (pin "4") (pinfunction "GND_4") (pintype "passive"))
      (node (ref "IC38") (pin "9") (pinfunction "PAD_9") (pintype "passive"))
      (node (ref "IC39") (pin "4") (pinfunction "GND_4") (pintype "passive"))
      (node (ref "IC39") (pin "9") (pinfunction "PAD_9") (pintype "passive"))
      (node (ref "IC40") (pin "4") (pinfunction "GND_4") (pintype "passive"))
      (node (ref "IC40") (pin "9") (pinfunction "PAD_9") (pintype "passive"))
      (node (ref "IC41") (pin "4") (pinfunction "SGND_4") (pintype "passive"))
      (node (ref "IC41") (pin "6") (pinfunction "PGND_6") (pintype "passive"))
      (node (ref "IC41") (pin "PAD") (pinfunction "PAD_(SGND)_PAD") (pintype "output"))
      (node (ref "J27") (pin "1") (pinfunction "1_1") (pintype "passive"))
      (node (ref "MECH5") (pin "MH1") (pinfunction "MH1_MH1") (pintype "passive"))
      (node (ref "MECH6") (pin "MH1") (pinfunction "MH1_MH1") (pintype "passive"))
      (node (ref "MECH7") (pin "MH1") (pinfunction "MH1_MH1") (pintype "passive"))
      (node (ref "MECH8") (pin "MH1") (pinfunction "MH1_MH1") (pintype "passive"))
      (node (ref "R233") (pin "1") (pinfunction "1_1") (pintype "passive"))
      (node (ref "R234") (pin "1") (pinfunction "1_1") (pintype "passive"))
      (node (ref "R239") (pin "2") (pinfunction "2_2") (pintype "passive"))
      (node (ref "R240") (pin "1") (pinfunction "1_1") (pintype "passive"))
      (node (ref "R241") (pin "1") (pinfunction "1_1") (pintype "passive"))
      (node (ref "R242") (pin "1") (pinfunction "1_1") (pintype "passive"))
      (node (ref "R246") (pin "2") (pinfunction "2_2") (pintype "passive"))
      (node (ref "R247") (pin "1") (pinfunction "1_1") (pintype "passive"))
      (node (ref "R249") (pin "1") (pinfunction "1_1") (pintype "passive"))
      (node (ref "T5") (pin "10") (pinfunction "10_10") (pintype "passive"))
      (node (ref "T5") (pin "9") (pinfunction "9_9") (pintype "passive"))
      (node (ref "VD7") (pin "A") (pinfunction "A_A") (pintype "passive"))
    )
    (net (code "13") (name "Net-(AT1-Anode)") (class "Default")
      (node (ref "AT1") (pin "1") (pinfunction "Anode_1") (pintype "passive"))
      (node (ref "C290") (pin "2") (pinfunction "2_2") (pintype "passive"))
      (node (ref "R221") (pin "2") (pinfunction "2_2") (pintype "passive"))
    )
    (net (code "14") (name "Net-(AT1-Cathode)") (class "Default")
      (node (ref "AT1") (pin "2") (pinfunction "Cathode_2") (pintype "passive"))
      (node (ref "R226") (pin "2") (pinfunction "2_2") (pintype "passive"))
    )
    (net (code "15") (name "Net-(C272-Pad1)") (class "Default")
      (node (ref "C272") (pin "1") (pinfunction "1_1") (pintype "passive"))
      (node (ref "D1") (pin "A") (pinfunction "A_A") (pintype "passive"))
      (node (ref "J26") (pin "1") (pinfunction "1_1") (pintype "passive"))
      (node (ref "R210") (pin "1") (pinfunction "1_1") (pintype "passive"))
      (node (ref "R211") (pin "1") (pinfunction "1_1") (pintype "passive"))
      (node (ref "R212") (pin "1") (pinfunction "1_1") (pintype "passive"))
      (node (ref "R215") (pin "2") (pinfunction "2_2") (pintype "passive"))
    )
    (net (code "16") (name "Net-(C278-Pad1)") (class "Default")
      (node (ref "C278") (pin "1") (pinfunction "1_1") (pintype "passive"))
      (node (ref "R219") (pin "2") (pinfunction "2_2") (pintype "passive"))
    )
    (net (code "17") (name "Net-(C284-Pad2)") (class "Default")
      (node (ref "C284") (pin "2") (pinfunction "2_2") (pintype "passive"))
      (node (ref "C285") (pin "2") (pinfunction "2_2") (pintype "passive"))
      (node (ref "L2") (pin "2") (pinfunction "2_2") (pintype "passive"))
      (node (ref "T5") (pin "3") (pinfunction "3_3") (pintype "passive"))
      (node (ref "VD6") (pin "K") (pinfunction "K_K") (pintype "passive"))
    )
    (net (code "18") (name "Net-(C292-Pad2)") (class "Default")
      (node (ref "C292") (pin "2") (pinfunction "2_2") (pintype "passive"))
      (node (ref "R223") (pin "1") (pinfunction "1_1") (pintype "passive"))
    )
    (net (code "19") (name "Net-(C295-Pad1)") (class "Default")
      (node (ref "C295") (pin "1") (pinfunction "1_1") (pintype "passive"))
      (node (ref "R227") (pin "1") (pinfunction "1_1") (pintype "passive"))
    )
    (net (code "20") (name "Net-(D2-PadC)") (class "Default")
      (node (ref "D2") (pin "C") (pinfunction "C_C") (pintype "passive"))
      (node (ref "VD6") (pin "A") (pinfunction "A_A") (pintype "passive"))
    )
    (net (code "21") (name "Net-(D3-PadA)") (class "Default")
      (node (ref "D3") (pin "A") (pinfunction "A_A") (pintype "passive"))
      (node (ref "R220") (pin "1") (pinfunction "1_1") (pintype "passive"))
    )
    (net (code "22") (name "Net-(D4-Cathode)") (class "Default")
      (node (ref "C291") (pin "2") (pinfunction "2_2") (pintype "passive"))
      (node (ref "C295") (pin "2") (pinfunction "2_2") (pintype "passive"))
      (node (ref "D4") (pin "3") (pinfunction "Cathode_3") (pintype "passive"))
      (node (ref "R226") (pin "1") (pinfunction "1_1") (pintype "passive"))
    )
    (net (code "23") (name "Net-(D4-Reference)") (class "Default")
      (node (ref "C291") (pin "1") (pinfunction "1_1") (pintype "passive"))
      (node (ref "D4") (pin "4") (pinfunction "Reference_4") (pintype "passive"))
      (node (ref "R222") (pin "1") (pinfunction "1_1") (pintype "passive"))
      (node (ref "R227") (pin "2") (pinfunction "2_2") (pintype "passive"))
      (node (ref "R233") (pin "2") (pinfunction "2_2") (pintype "passive"))
      (node (ref "R234") (pin "2") (pinfunction "2_2") (pintype "passive"))
    )
    (net (code "24") (name "Net-(IC34-AUXI_IRL)") (class "Default")
      (node (ref "C275") (pin "2") (pinfunction "2_2") (pintype "passive"))
      (node (ref "IC34") (pin "6") (pinfunction "AUXI_IRL_6") (pintype "passive"))
    )
    (net (code "25") (name "Net-(IC34-DCCL)") (class "Default")
      (node (ref "IC34") (pin "7") (pinfunction "DCCL_7") (pintype "passive"))
      (node (ref "R217") (pin "1") (pinfunction "1_1") (pintype "passive"))
    )
    (net (code "26") (name "Net-(IC34-RCLASS)") (class "Default")
      (node (ref "IC34") (pin "5") (pinfunction "RCLASS_5") (pintype "passive"))
      (node (ref "R214") (pin "1") (pinfunction "1_1") (pintype "passive"))
    )
    (net (code "27") (name "Net-(IC34-RT)") (class "Default")
      (node (ref "IC34") (pin "1") (pinfunction "RT_1") (pintype "passive"))
      (node (ref "R209") (pin "2") (pinfunction "2_2") (pintype "passive"))
    )
    (net (code "28") (name "Net-(IC34-SS)") (class "Default")
      (node (ref "C270") (pin "2") (pinfunction "2_2") (pintype "passive"))
      (node (ref "IC34") (pin "2") (pinfunction "SS_2") (pintype "passive"))
    )
    (net (code "29") (name "Net-(IC34-VIN)") (class "Default")
      (node (ref "C271") (pin "2") (pinfunction "2_2") (pintype "passive"))
      (node (ref "IC34") (pin "4") (pinfunction "VIN_4") (pintype "passive"))
      (node (ref "R208") (pin "1") (pinfunction "1_1") (pintype "passive"))
    )
    (net (code "30") (name "Net-(IC35-VCON)") (class "Default")
      (node (ref "C306") (pin "1") (pinfunction "1_1") (pintype "passive"))
      (node (ref "IC35") (pin "2") (pinfunction "VCON_2") (pintype "input"))
      (node (ref "R237") (pin "1") (pinfunction "1_1") (pintype "passive"))
      (node (ref "R241") (pin "2") (pinfunction "2_2") (pintype "passive"))
    )
    (net (code "31") (name "Net-(IC35-VREF)") (class "Default")
      (node (ref "IC35") (pin "8") (pinfunction "VREF_8") (pintype "output"))
      (node (ref "R237") (pin "2") (pinfunction "2_2") (pintype "passive"))
    )
    (net (code "32") (name "Net-(IC36-VCON)") (class "Default")
      (node (ref "C307") (pin "1") (pinfunction "1_1") (pintype "passive"))
      (node (ref "IC36") (pin "2") (pinfunction "VCON_2") (pintype "input"))
      (node (ref "R238") (pin "1") (pinfunction "1_1") (pintype "passive"))
      (node (ref "R242") (pin "2") (pinfunction "2_2") (pintype "passive"))
    )
    (net (code "33") (name "Net-(IC36-VREF)") (class "Default")
      (node (ref "IC36") (pin "8") (pinfunction "VREF_8") (pintype "output"))
      (node (ref "R238") (pin "2") (pinfunction "2_2") (pintype "passive"))
    )
    (net (code "34") (name "Net-(IC37-ADJ{slash}NC)") (class "Default")
      (node (ref "IC37") (pin "3") (pinfunction "ADJ/NC_3") (pintype "passive"))
      (node (ref "R235") (pin "1") (pinfunction "1_1") (pintype "passive"))
      (node (ref "R239") (pin "1") (pinfunction "1_1") (pintype "passive"))
    )
    (net (code "35") (name "Net-(IC37-EN)") (class "Default")
      (node (ref "C302") (pin "2") (pinfunction "2_2") (pintype "passive"))
      (node (ref "FR47") (pin "2") (pinfunction "2_2") (pintype "passive"))
      (node (ref "IC37") (pin "5") (pinfunction "EN_5") (pintype "input"))
      (node (ref "IC37") (pin "8") (pinfunction "IN_8") (pintype "input"))
    )
    (net (code "36") (name "Net-(IC38-ADJ{slash}NC)") (class "Default")
      (node (ref "IC38") (pin "3") (pinfunction "ADJ/NC_3") (pintype "passive"))
      (node (ref "R236") (pin "1") (pinfunction "1_1") (pintype "passive"))
      (node (ref "R240") (pin "2") (pinfunction "2_2") (pintype "passive"))
    )
    (net (code "37") (name "Net-(IC38-EN)") (class "Default")
      (node (ref "C304") (pin "2") (pinfunction "2_2") (pintype "passive"))
      (node (ref "FR48") (pin "2") (pinfunction "2_2") (pintype "passive"))
      (node (ref "IC38") (pin "5") (pinfunction "EN_5") (pintype "input"))
      (node (ref "IC38") (pin "8") (pinfunction "IN_8") (pintype "input"))
    )
    (net (code "38") (name "Net-(IC39-ADJ{slash}NC)") (class "Default")
      (node (ref "IC39") (pin "3") (pinfunction "ADJ/NC_3") (pintype "passive"))
      (node (ref "R243") (pin "1") (pinfunction "1_1") (pintype "passive"))
      (node (ref "R246") (pin "1") (pinfunction "1_1") (pintype "passive"))
    )
    (net (code "39") (name "Net-(IC39-EN)") (class "Default")
      (node (ref "C308") (pin "2") (pinfunction "2_2") (pintype "passive"))
      (node (ref "FR49") (pin "2") (pinfunction "2_2") (pintype "passive"))
      (node (ref "IC39") (pin "5") (pinfunction "EN_5") (pintype "input"))
      (node (ref "IC39") (pin "8") (pinfunction "IN_8") (pintype "input"))
    )
    (net (code "40") (name "Net-(IC40-ADJ{slash}NC)") (class "Default")
      (node (ref "IC40") (pin "3") (pinfunction "ADJ/NC_3") (pintype "passive"))
      (node (ref "R244") (pin "2") (pinfunction "2_2") (pintype "passive"))
      (node (ref "R247") (pin "2") (pinfunction "2_2") (pintype "passive"))
    )
    (net (code "41") (name "Net-(IC40-EN)") (class "Default")
      (node (ref "C310") (pin "2") (pinfunction "2_2") (pintype "passive"))
      (node (ref "FR50") (pin "2") (pinfunction "2_2") (pintype "passive"))
      (node (ref "IC40") (pin "5") (pinfunction "EN_5") (pintype "input"))
      (node (ref "IC40") (pin "8") (pinfunction "IN_8") (pintype "input"))
    )
    (net (code "42") (name "Net-(IC41-EN)") (class "Default")
      (node (ref "IC41") (pin "1") (pinfunction "EN_1") (pintype "input"))
      (node (ref "R245") (pin "2") (pinfunction "2_2") (pintype "passive"))
    )
    (net (code "43") (name "Net-(IC41-VCON)") (class "Default")
      (node (ref "C315") (pin "1") (pinfunction "1_1") (pintype "passive"))
      (node (ref "IC41") (pin "2") (pinfunction "VCON_2") (pintype "input"))
      (node (ref "R248") (pin "1") (pinfunction "1_1") (pintype "passive"))
      (node (ref "R249") (pin "2") (pinfunction "2_2") (pintype "passive"))
    )
    (net (code "44") (name "Net-(IC41-VREF)") (class "Default")
      (node (ref "IC41") (pin "8") (pinfunction "VREF_8") (pintype "output"))
      (node (ref "R248") (pin "2") (pinfunction "2_2") (pintype "passive"))
    )
    (net (code "45") (name "Net-(R220-Pad2)") (class "Default")
      (node (ref "R220") (pin "2") (pinfunction "2_2") (pintype "passive"))
      (node (ref "T5") (pin "2") (pinfunction "2_2") (pintype "passive"))
    )
    (net (code "46") (name "Net-(VD4-A)") (class "Default")
      (node (ref "C273") (pin "1") (pinfunction "1_1") (pintype "passive"))
      (node (ref "J26") (pin "2") (pinfunction "2_2") (pintype "passive"))
      (node (ref "J26") (pin "3") (pinfunction "3_3") (pintype "passive"))
      (node (ref "R215") (pin "1") (pinfunction "1_1") (pintype "passive"))
      (node (ref "R218") (pin "2") (pinfunction "2_2") (pintype "passive"))
      (node (ref "VD4") (pin "1") (pinfunction "A_1") (pintype "passive"))
      (node (ref "VT8") (pin "1") (pinfunction "S_1") (pintype "passive"))
      (node (ref "VT8") (pin "2") (pinfunction "S_2") (pintype "passive"))
      (node (ref "VT8") (pin "3") (pinfunction "S_3") (pintype "passive"))
    )
    (net (code "47") (name "Net-(VD4-C)") (class "Default")
      (node (ref "R211") (pin "2") (pinfunction "2_2") (pintype "passive"))
      (node (ref "R213") (pin "2") (pinfunction "2_2") (pintype "passive"))
      (node (ref "VD4") (pin "3") (pinfunction "C_3") (pintype "passive"))
    )
    (net (code "48") (name "Net-(VD5-A1)") (class "Default")
      (node (ref "R219") (pin "1") (pinfunction "1_1") (pintype "passive"))
      (node (ref "T5") (pin "7") (pinfunction "7_7") (pintype "passive"))
      (node (ref "T5") (pin "8") (pinfunction "8_8") (pintype "passive"))
      (node (ref "VD5") (pin "1") (pinfunction "A1_1") (pintype "passive"))
      (node (ref "VD5") (pin "3") (pinfunction "A2_3") (pintype "passive"))
    )
    (net (code "49") (name "Net-(VD5-C)") (class "Default")
      (node (ref "C278") (pin "2") (pinfunction "2_2") (pintype "passive"))
      (node (ref "C286") (pin "2") (pinfunction "2_2") (pintype "passive"))
      (node (ref "L3") (pin "1") (pinfunction "1_1") (pintype "passive"))
      (node (ref "VD5") (pin "4") (pinfunction "C_4") (pintype "passive"))
    )
    (net (code "50") (name "Net-(VT8-G)") (class "Default")
      (node (ref "C273") (pin "2") (pinfunction "2_2") (pintype "passive"))
      (node (ref "R212") (pin "2") (pinfunction "2_2") (pintype "passive"))
      (node (ref "R213") (pin "1") (pinfunction "1_1") (pintype "passive"))
      (node (ref "R218") (pin "1") (pinfunction "1_1") (pintype "passive"))
      (node (ref "VT8") (pin "4") (pinfunction "G_4") (pintype "passive"))
    )
    (net (code "51") (name "Net-(VT9-D)") (class "Default")
      (node (ref "D2") (pin "A") (pinfunction "A_A") (pintype "passive"))
      (node (ref "T5") (pin "4") (pinfunction "4_4") (pintype "passive"))
      (node (ref "VT9") (pin "4") (pinfunction "D_4") (pintype "passive"))
    )
    (net (code "52") (name "Net-(VT9-G)") (class "Default")
      (node (ref "R225") (pin "2") (pinfunction "2_2") (pintype "passive"))
      (node (ref "R230") (pin "1") (pinfunction "1_1") (pintype "passive"))
      (node (ref "VT9") (pin "1") (pinfunction "G_1") (pintype "passive"))
    )
    (net (code "53") (name "Net-(VT9-S)") (class "Default")
      (node (ref "R228") (pin "2") (pinfunction "2_2") (pintype "passive"))
      (node (ref "R231") (pin "1") (pinfunction "1_1") (pintype "passive"))
      (node (ref "R232") (pin "1") (pinfunction "1_1") (pintype "passive"))
      (node (ref "VT9") (pin "3") (pinfunction "S_3") (pintype "passive"))
    )
    (net (code "54") (name "POE_AGND") (class "Default")
      (node (ref "AT1") (pin "3") (pinfunction "Emitter_3") (pintype "passive"))
      (node (ref "C270") (pin "1") (pinfunction "1_1") (pintype "passive"))
      (node (ref "C276") (pin "1") (pinfunction "1_1") (pintype "passive"))
      (node (ref "C294") (pin "1") (pinfunction "1_1") (pintype "passive"))
      (node (ref "IC34") (pin "16") (pinfunction "AGND_16") (pintype "passive"))
      (node (ref "R209") (pin "1") (pinfunction "1_1") (pintype "passive"))
      (node (ref "R229") (pin "2") (pinfunction "2_2") (pintype "passive"))
    )
    (net (code "55") (name "POE_GND") (class "Default")
      (node (ref "C272") (pin "2") (pinfunction "2_2") (pintype "passive"))
      (node (ref "C277") (pin "1") (pinfunction "1_1") (pintype "passive"))
      (node (ref "C280") (pin "1") (pinfunction "1_1") (pintype "passive"))
      (node (ref "C281") (pin "1") (pinfunction "1_1") (pintype "passive"))
      (node (ref "C282") (pin "1") (pinfunction "1_1") (pintype "passive"))
      (node (ref "C283") (pin "1") (pinfunction "1_1") (pintype "passive"))
      (node (ref "C284") (pin "1") (pinfunction "1_1") (pintype "passive"))
      (node (ref "C285") (pin "1") (pinfunction "1_1") (pintype "passive"))
      (node (ref "C293") (pin "1") (pinfunction "1_1") (pintype "passive"))
      (node (ref "C296") (pin "2") (pinfunction "2_2") (pintype "passive"))
      (node (ref "C297") (pin "2") (pinfunction "2_2") (pintype "passive"))
      (node (ref "IC34") (pin "9") (pinfunction "GND_9") (pintype "passive"))
      (node (ref "R230") (pin "2") (pinfunction "2_2") (pintype "passive"))
      (node (ref "R231") (pin "2") (pinfunction "2_2") (pintype "passive"))
      (node (ref "R232") (pin "2") (pinfunction "2_2") (pintype "passive"))
      (node (ref "T5") (pin "1") (pinfunction "1_1") (pintype "passive"))
      (node (ref "VT8") (pin "5") (pinfunction "D_5") (pintype "passive"))
      (node (ref "VT8") (pin "6") (pinfunction "D_6") (pintype "passive"))
      (node (ref "VT8") (pin "7") (pinfunction "D_7") (pintype "passive"))
      (node (ref "VT8") (pin "8") (pinfunction "D_8") (pintype "passive"))
    )
    (net (code "56") (name "POE_VIN") (class "Default")
      (node (ref "BR1") (pin "1") (pinfunction "V+_1") (pintype "passive"))
      (node (ref "BR2") (pin "1") (pinfunction "V+_1") (pintype "passive"))
      (node (ref "C274") (pin "2") (pinfunction "2_2") (pintype "passive"))
      (node (ref "C280") (pin "2") (pinfunction "2_2") (pintype "passive"))
      (node (ref "C281") (pin "2") (pinfunction "2_2") (pintype "passive"))
      (node (ref "C282") (pin "2") (pinfunction "2_2") (pintype "passive"))
      (node (ref "C283") (pin "2") (pinfunction "2_2") (pintype "passive"))
      (node (ref "D1") (pin "C") (pinfunction "C_C") (pintype "passive"))
      (node (ref "L2") (pin "1") (pinfunction "1_1") (pintype "passive"))
      (node (ref "R208") (pin "2") (pinfunction "2_2") (pintype "passive"))
      (node (ref "VD3") (pin "A") (pinfunction "A_A") (pintype "passive"))
    )
    (net (code "57") (name "POE_VSS") (class "Default")
      (node (ref "BR1") (pin "2") (pinfunction "V-_2") (pintype "passive"))
      (node (ref "BR2") (pin "2") (pinfunction "V-_2") (pintype "passive"))
      (node (ref "C271") (pin "1") (pinfunction "1_1") (pintype "passive"))
      (node (ref "C274") (pin "1") (pinfunction "1_1") (pintype "passive"))
      (node (ref "C275") (pin "1") (pinfunction "1_1") (pintype "passive"))
      (node (ref "C277") (pin "2") (pinfunction "2_2") (pintype "passive"))
      (node (ref "IC34") (pin "17") (pinfunction "GPAD_17") (pintype "passive"))
      (node (ref "IC34") (pin "8") (pinfunction "VSS_8") (pintype "passive"))
      (node (ref "R214") (pin "2") (pinfunction "2_2") (pintype "passive"))
      (node (ref "R217") (pin "2") (pinfunction "2_2") (pintype "passive"))
      (node (ref "VD3") (pin "K") (pinfunction "K_K") (pintype "passive"))
    )
    (net (code "58") (name "VCC1P4_LMS") (class "Default")
      (node (ref "C311") (pin "2") (pinfunction "2_2") (pintype "passive"))
      (node (ref "IC40") (pin "1") (pinfunction "OUT_1") (pintype "output"))
      (node (ref "R244") (pin "1") (pinfunction "1_1") (pintype "passive"))
    )
    (net (code "59") (name "VCC1P8") (class "Default")
      (node (ref "C313") (pin "2") (pinfunction "2_2") (pintype "passive"))
      (node (ref "FR51") (pin "1") (pinfunction "1_1") (pintype "passive"))
      (node (ref "IC41") (pin "3") (pinfunction "FB_3") (pintype "input"))
      (node (ref "IC41") (pin "5") (pinfunction "VOUT_5") (pintype "output"))
    )
    (net (code "60") (name "VCC1P8_LMS") (class "Default")
      (node (ref "C314") (pin "2") (pinfunction "2_2") (pintype "passive"))
      (node (ref "FR48") (pin "1") (pinfunction "1_1") (pintype "passive"))
      (node (ref "FR50") (pin "1") (pinfunction "1_1") (pintype "passive"))
      (node (ref "FR51") (pin "2") (pinfunction "2_2") (pintype "passive"))
    )
    (net (code "61") (name "VCC1P25_LMS") (class "Default")
      (node (ref "C305") (pin "2") (pinfunction "2_2") (pintype "passive"))
      (node (ref "IC38") (pin "1") (pinfunction "OUT_1") (pintype "output"))
      (node (ref "R236") (pin "2") (pinfunction "2_2") (pintype "passive"))
    )
    (net (code "62") (name "VCC2P5") (class "Default")
      (node (ref "C303") (pin "2") (pinfunction "2_2") (pintype "passive"))
      (node (ref "IC37") (pin "1") (pinfunction "OUT_1") (pintype "output"))
      (node (ref "R235") (pin "2") (pinfunction "2_2") (pintype "passive"))
    )
    (net (code "63") (name "VCC3P3") (class "Default")
      (node (ref "C299") (pin "2") (pinfunction "2_2") (pintype "passive"))
      (node (ref "IC35") (pin "3") (pinfunction "FB_3") (pintype "input"))
      (node (ref "IC35") (pin "5") (pinfunction "VOUT_5") (pintype "output"))
      (node (ref "R245") (pin "1") (pinfunction "1_1") (pintype "passive"))
      (node (ref "R250") (pin "2") (pinfunction "2_2") (pintype "passive"))
      (node (ref "R251") (pin "2") (pinfunction "2_2") (pintype "passive"))
    )
    (net (code "64") (name "VCC3P3_2") (class "Default")
      (node (ref "C301") (pin "2") (pinfunction "2_2") (pintype "passive"))
      (node (ref "IC36") (pin "3") (pinfunction "FB_3") (pintype "input"))
      (node (ref "IC36") (pin "5") (pinfunction "VOUT_5") (pintype "output"))
      (node (ref "R250") (pin "1") (pinfunction "1_1") (pintype "passive"))
    )
    (net (code "65") (name "VCC3P3_CLK") (class "Default")
      (node (ref "C309") (pin "2") (pinfunction "2_2") (pintype "passive"))
      (node (ref "IC39") (pin "1") (pinfunction "OUT_1") (pintype "output"))
      (node (ref "R243") (pin "2") (pinfunction "2_2") (pintype "passive"))
      (node (ref "R251") (pin "1") (pinfunction "1_1") (pintype "passive"))
    )
    (net (code "66") (name "VCC5P0") (class "Default")
      (node (ref "C298") (pin "2") (pinfunction "2_2") (pintype "passive"))
      (node (ref "C300") (pin "2") (pinfunction "2_2") (pintype "passive"))
      (node (ref "C312") (pin "2") (pinfunction "2_2") (pintype "passive"))
      (node (ref "FR47") (pin "1") (pinfunction "1_1") (pintype "passive"))
      (node (ref "FR49") (pin "1") (pinfunction "1_1") (pintype "passive"))
      (node (ref "IC35") (pin "7") (pinfunction "VIN_7") (pintype "input"))
      (node (ref "IC36") (pin "7") (pinfunction "VIN_7") (pintype "input"))
      (node (ref "IC41") (pin "7") (pinfunction "VIN_7") (pintype "input"))
      (node (ref "J27") (pin "2") (pinfunction "2_2") (pintype "passive"))
      (node (ref "J28") (pin "2") (pinfunction "2_2") (pintype "passive"))
      (node (ref "R224") (pin "1") (pinfunction "1_1") (pintype "passive"))
      (node (ref "VD7") (pin "K") (pinfunction "K_K") (pintype "passive"))
    )
    (net (code "67") (name "VCC5P0_POE") (class "Default")
      (node (ref "C279") (pin "2") (pinfunction "2_2") (pintype "passive"))
      (node (ref "C287") (pin "2") (pinfunction "2_2") (pintype "passive"))
      (node (ref "C288") (pin "2") (pinfunction "2_2") (pintype "passive"))
      (node (ref "C289") (pin "2") (pinfunction "2_2") (pintype "passive"))
      (node (ref "J28") (pin "1") (pinfunction "1_1") (pintype "passive"))
      (node (ref "L3") (pin "2") (pinfunction "2_2") (pintype "passive"))
      (node (ref "R221") (pin "1") (pinfunction "1_1") (pintype "passive"))
      (node (ref "R222") (pin "2") (pinfunction "2_2") (pintype "passive"))
      (node (ref "R224") (pin "2") (pinfunction "2_2") (pintype "passive"))
    )
    (net (code "68") (name "VCC5P0_USB_EXT") (class "Default")
      (node (ref "J28") (pin "3") (pinfunction "3_3") (pintype "passive"))
    )
    (net (code "69") (name "unconnected-(D4-NC-Pad1)") (class "Default")
      (node (ref "D4") (pin "1") (pinfunction "NC_1") (pintype "passive+no_connect"))
    )
    (net (code "70") (name "unconnected-(D4-NC-Pad2)") (class "Default")
      (node (ref "D4") (pin "2") (pinfunction "NC_2") (pintype "passive+no_connect"))
    )
    (net (code "71") (name "unconnected-(F1-Pad1)") (class "Default")
      (node (ref "F1") (pin "1") (pintype "passive+no_connect"))
    )
    (net (code "72") (name "unconnected-(F2-Pad1)") (class "Default")
      (node (ref "F2") (pin "1") (pintype "passive+no_connect"))
    )
    (net (code "73") (name "unconnected-(F3-Pad1)") (class "Default")
      (node (ref "F3") (pin "1") (pintype "passive+no_connect"))
    )
    (net (code "74") (name "unconnected-(F4-Pad1)") (class "Default")
      (node (ref "F4") (pin "1") (pintype "passive+no_connect"))
    )
    (net (code "75") (name "unconnected-(F5-Pad1)") (class "Default")
      (node (ref "F5") (pin "1") (pintype "passive+no_connect"))
    )
    (net (code "76") (name "unconnected-(F6-Pad1)") (class "Default")
      (node (ref "F6") (pin "1") (pintype "passive+no_connect"))
    )
    (net (code "77") (name "unconnected-(F7-Pad1)") (class "Default")
      (node (ref "F7") (pin "1") (pintype "passive+no_connect"))
    )
    (net (code "78") (name "unconnected-(F8-Pad1)") (class "Default")
      (node (ref "F8") (pin "1") (pintype "passive+no_connect"))
    )
    (net (code "79") (name "unconnected-(IC35-EN-Pad1)") (class "Default")
      (node (ref "IC35") (pin "1") (pinfunction "EN_1") (pintype "input+no_connect"))
    )
    (net (code "80") (name "unconnected-(IC36-EN-Pad1)") (class "Default")
      (node (ref "IC36") (pin "1") (pinfunction "EN_1") (pintype "input+no_connect"))
    )
    (net (code "81") (name "unconnected-(IC37-NC-Pad2)") (class "Default")
      (node (ref "IC37") (pin "2") (pinfunction "NC_2") (pintype "passive+no_connect"))
    )
    (net (code "82") (name "unconnected-(IC37-NC-Pad6)") (class "Default")
      (node (ref "IC37") (pin "6") (pinfunction "NC_6") (pintype "passive+no_connect"))
    )
    (net (code "83") (name "unconnected-(IC37-NC-Pad7)") (class "Default")
      (node (ref "IC37") (pin "7") (pinfunction "NC_7") (pintype "passive+no_connect"))
    )
    (net (code "84") (name "unconnected-(IC38-NC-Pad2)") (class "Default")
      (node (ref "IC38") (pin "2") (pinfunction "NC_2") (pintype "passive+no_connect"))
    )
    (net (code "85") (name "unconnected-(IC38-NC-Pad6)") (class "Default")
      (node (ref "IC38") (pin "6") (pinfunction "NC_6") (pintype "passive+no_connect"))
    )
    (net (code "86") (name "unconnected-(IC38-NC-Pad7)") (class "Default")
      (node (ref "IC38") (pin "7") (pinfunction "NC_7") (pintype "passive+no_connect"))
    )
    (net (code "87") (name "unconnected-(IC39-NC-Pad2)") (class "Default")
      (node (ref "IC39") (pin "2") (pinfunction "NC_2") (pintype "passive+no_connect"))
    )
    (net (code "88") (name "unconnected-(IC39-NC-Pad6)") (class "Default")
      (node (ref "IC39") (pin "6") (pinfunction "NC_6") (pintype "passive+no_connect"))
    )
    (net (code "89") (name "unconnected-(IC39-NC-Pad7)") (class "Default")
      (node (ref "IC39") (pin "7") (pinfunction "NC_7") (pintype "passive+no_connect"))
    )
    (net (code "90") (name "unconnected-(IC40-NC-Pad2)") (class "Default")
      (node (ref "IC40") (pin "2") (pinfunction "NC_2") (pintype "passive+no_connect"))
    )
    (net (code "91") (name "unconnected-(IC40-NC-Pad6)") (class "Default")
      (node (ref "IC40") (pin "6") (pinfunction "NC_6") (pintype "passive+no_connect"))
    )
    (net (code "92") (name "unconnected-(IC40-NC-Pad7)") (class "Default")
      (node (ref "IC40") (pin "7") (pinfunction "NC_7") (pintype "passive+no_connect"))
    )
  )
)
